# Power_Supply.net
KiCad netlist of a schematic drawn in Altium Designer
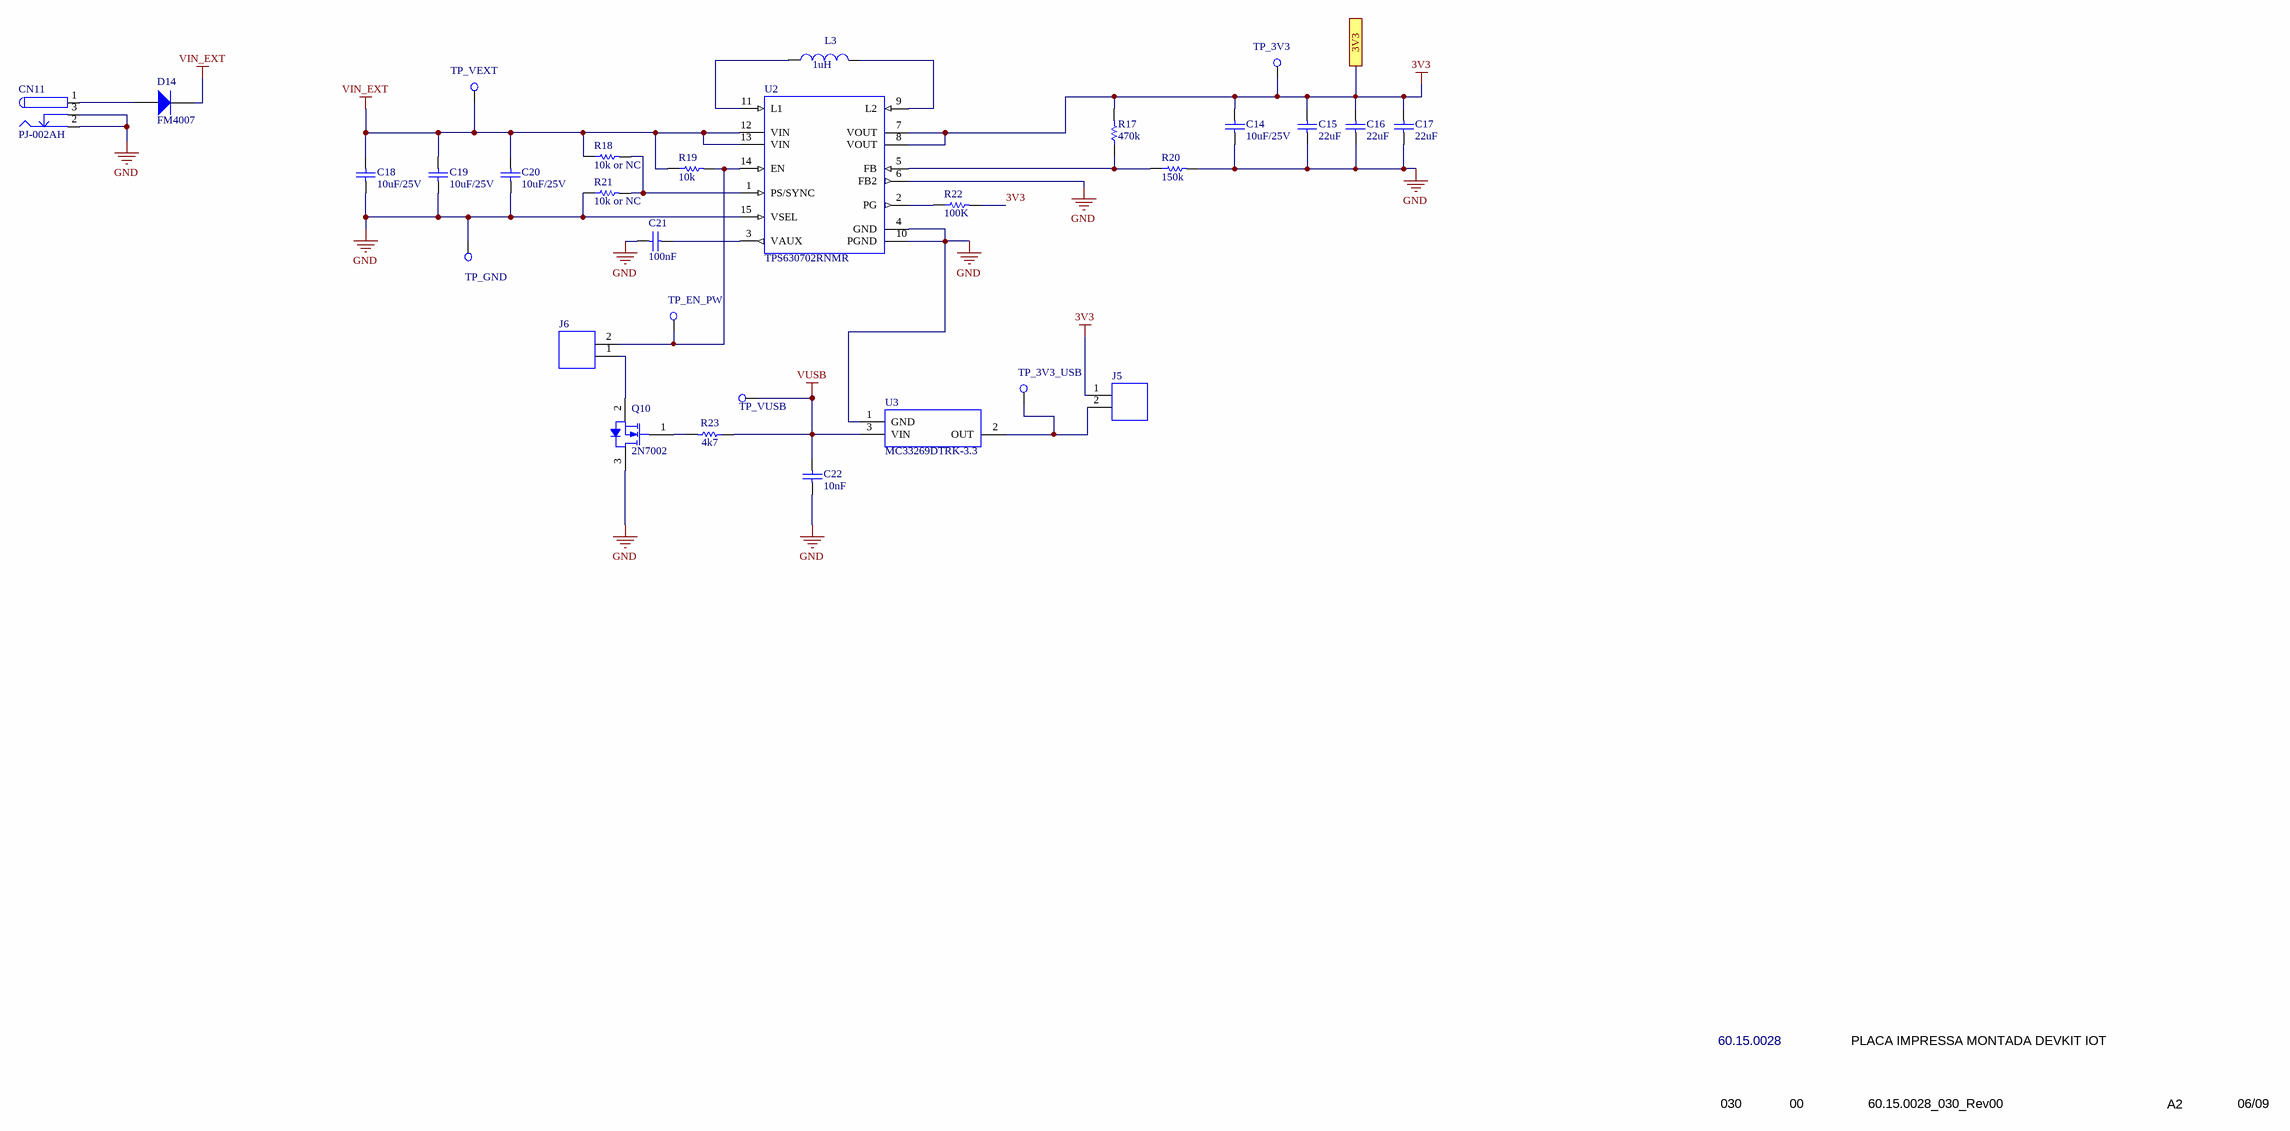
[diagram p0: Power Supply.SchDoc]

(export (version "E")
  (design (tool "Eeschema 10.0.6"))
  (components
    (comp (ref "C14")
      (value "10uF/25V")
      (footprint "16.23.0733")
      (description "CAPACITOR CERAMICO MULTICAMADAS 10uF 25V 20% SMD 0603 X5R")
      (fields (field (name "PART NUMBER") "GRM188R61E106MA73") (field (name "Comment") "16.23.0733"))
      (libsource (lib "OMNI-CAPACITORES") (part "16.23.0733"))
    )
    (comp (ref "C15")
      (value "16.23.0428")
      (footprint "16.23.0428")
      (description "CC MUL 22uF 16V X5R 20% SMD 0805")
      (fields (field (name "ALTIUM_UNNAMED_1") "22uF"))
      (libsource (lib "OMNI-CAPACITORES") (part "16.23.0428"))
    )
    (comp (ref "C16")
      (value "16.23.0428")
      (footprint "16.23.0428")
      (description "CC MUL 22uF 16V X5R 20% SMD 0805")
      (fields (field (name "ALTIUM_UNNAMED_1") "22uF"))
      (libsource (lib "OMNI-CAPACITORES") (part "16.23.0428"))
    )
    (comp (ref "C17")
      (value "16.23.0428")
      (footprint "16.23.0428")
      (description "CC MUL 22uF 16V X5R 20% SMD 0805")
      (fields (field (name "ALTIUM_UNNAMED_1") "22uF"))
      (libsource (lib "OMNI-CAPACITORES") (part "16.23.0428"))
    )
    (comp (ref "C18")
      (value "10uF/25V")
      (footprint "16.23.0735")
      (description "CAPACITOR CERAMICO MULTICAMADAS 10uF 25V 10% SMD 0805 X5R")
      (fields (field (name "PART NUMBER") "GRM21BR61E106KA73") (field (name "Comment") "16.23.0735"))
      (libsource (lib "OMNI-CAPACITORES") (part "16.23.0735"))
    )
    (comp (ref "C19")
      (value "10uF/25V")
      (footprint "16.23.0735")
      (description "CAPACITOR CERAMICO MULTICAMADAS 10uF 25V 10% SMD 0805 X5R")
      (fields (field (name "PART NUMBER") "GRM21BR61E106KA73") (field (name "Comment") "16.23.0735"))
      (libsource (lib "OMNI-CAPACITORES") (part "16.23.0735"))
    )
    (comp (ref "C20")
      (value "10uF/25V")
      (footprint "16.23.0733")
      (description "CAPACITOR CERAMICO MULTICAMADAS 10uF 25V 20% SMD 0603 X5R")
      (fields (field (name "PART NUMBER") "GRM188R61E106MA73") (field (name "Comment") "16.23.0733"))
      (libsource (lib "OMNI-CAPACITORES") (part "16.23.0733"))
    )
    (comp (ref "C21")
      (value "100nF")
      (footprint "16.23.0807")
      (description "CAPACITOR CERAMICO MULTICAMADAS 100nF 50V X7R 10% SMD 0402")
      (fields (field (name "Comment") "16.23.0807"))
      (libsource (lib "OMNI-CAPACITORES") (part "16.23.0807"))
    )
    (comp (ref "C22")
      (value "16.23.0427")
      (footprint "16.23.0427")
      (description "CC MUL 10nF 16V C0G 10%  SMD 0402")
      (fields (field (name "ALTIUM_UNNAMED_1") "10nF"))
      (libsource (lib "OMNI-CAPACITORES") (part "16.23.0427"))
    )
    (comp (ref "CN11")
      (value "28.39.0015")
      (footprint "28.39.0015")
      (description "CONECTOR ALIMENTACAO JACK  MODEL PJ-002AH - SMT -TR")
      (fields (field (name "CUI INC") "PJ-002AH"))
      (libsource (lib "OMNI-CONECTORES") (part "28.39.0015"))
    )
    (comp (ref "D14")
      (value "FM4007")
      (footprint "32.21.0028")
      (description "DIODO RETIFICADOR 1A 1000V 1N4007 SMD DO-214AC")
      (fields (field (name "Comment") "32.21.0028"))
      (libsource (lib "OMNI-DIODOS_LED´s_DISPLAYS") (part "32.21.0028"))
    )
    (comp (ref "J5")
      (value "70.11.0010")
      (footprint "70.11.0010")
      (description "BARRA DE TERMINAIS 1x2")
      (libsource (lib "") (part "70.11.0010_1"))
    )
    (comp (ref "J6")
      (value "70.11.0010")
      (footprint "70.11.0010")
      (description "BARRA DE TERMINAIS 1x2")
      (libsource (lib "OMNI-CONECTORES") (part "70.11.0010"))
    )
    (comp (ref "L3")
      (value "1uH")
      (footprint "40.12.0346")
      (description "INDUTOR FIXO 1uH 20% 5A 36mOHM SMD 1008")
      (fields (field (name "Comment") "40.12.0346"))
      (libsource (lib "OMNI-INDUTORES") (part "40.12.0346"))
    )
    (comp (ref "Q10")
      (value "72.19.0021")
      (footprint "72.19.0021")
      (description "TRANSISTOR MOSFET N 60V 115MA 0.2W SMD")
      (fields (field (name "ALTIUM_UNNAMED_1") "2N7002"))
      (libsource (lib "OMNI-TRANSISTORES") (part "72.19.0021"))
    )
    (comp (ref "R17")
      (value "470k")
      (footprint "66.21.1644")
      (description "RESISTOR THICK FILM 470k OHMS 25V 0.05W 1% SMD 0201")
      (fields (field (name "Comment") "66.21.1644"))
      (libsource (lib "OMNI-RESISTORES") (part "66.21.1644"))
    )
    (comp (ref "R18")
      (value "10k or NC")
      (footprint "66.21.1646")
      (description "RESISTOR THICK FILM 10k OHMS 25V 0.05W 1% SMD 0201")
      (fields (field (name "Comment") "66.21.1646"))
      (libsource (lib "OMNI-RESISTORES") (part "66.21.1646"))
    )
    (comp (ref "R19")
      (value "10k")
      (footprint "66.21.1646")
      (description "RESISTOR THICK FILM 10k OHMS 25V 0.05W 1% SMD 0201")
      (fields (field (name "Comment") "66.21.1646"))
      (libsource (lib "OMNI-RESISTORES") (part "66.21.1646"))
    )
    (comp (ref "R20")
      (value "150k")
      (footprint "66.21.1645")
      (description "RESISTOR THICK FILM 150k OHMS 25V 0.05W 1% SMD 0201")
      (fields (field (name "Comment") "66.21.1645"))
      (libsource (lib "OMNI-RESISTORES") (part "66.21.1645"))
    )
    (comp (ref "R21")
      (value "10k or NC")
      (footprint "66.21.1646")
      (description "RESISTOR THICK FILM 10k OHMS 25V 0.05W 1% SMD 0201")
      (fields (field (name "Comment") "66.21.1646"))
      (libsource (lib "OMNI-RESISTORES") (part "66.21.1646"))
    )
    (comp (ref "R22")
      (value "100K")
      (footprint "66.24.1346")
      (description "RESISTOR THICK FILM 50mW 100K OHMS 1% SMD 0201")
      (fields (field (name "Comment") "66.24.1346"))
      (libsource (lib "OMNI-RESISTORES") (part "66.24.1346"))
    )
    (comp (ref "R23")
      (value "4k7")
      (footprint "66.24.1353")
      (description "RESISTOR THICK FILM 4k7 kOHMS 50V 0,1W 1% SMD 0402")
      (fields (field (name "PART NUMBER") "ERJ-2RKF4701X") (field (name "Comment") "66.24.1353"))
      (libsource (lib "OMNI-RESISTORES") (part "66.24.1353"))
    )
    (comp (ref "TP_3V3")
      (value "TESTPOINT")
      (footprint "TESTPOINT-60MILS")
      (description "PONTO DE TESTE PARA CAMA DE PREGO")
      (libsource (lib "OMNI-SEM-COD") (part "TESTPOINT-60MILS"))
    )
    (comp (ref "TP_3V3_USB")
      (value "TESTPOINT")
      (footprint "TESTPOINT-60MILS")
      (description "PONTO DE TESTE PARA CAMA DE PREGO")
      (libsource (lib "OMNI-SEM-COD") (part "TESTPOINT-60MILS"))
    )
    (comp (ref "TP_EN_PW")
      (value "TESTPOINT")
      (footprint "TESTPOINT-60MILS")
      (description "PONTO DE TESTE PARA CAMA DE PREGO")
      (libsource (lib "OMNI-SEM-COD") (part "TESTPOINT-60MILS"))
    )
    (comp (ref "TP_GND")
      (value "TESTPOINT")
      (footprint "TESTPOINT-60MILS")
      (description "PONTO DE TESTE PARA CAMA DE PREGO")
      (libsource (lib "OMNI-SEM-COD") (part "TESTPOINT-60MILS"))
    )
    (comp (ref "TP_VEXT")
      (value "TESTPOINT")
      (footprint "TESTPOINT-60MILS")
      (description "PONTO DE TESTE PARA CAMA DE PREGO")
      (libsource (lib "OMNI-SEM-COD") (part "TESTPOINT-60MILS"))
    )
    (comp (ref "TP_VUSB")
      (value "TESTPOINT")
      (footprint "TESTPOINT-60MILS")
      (description "PONTO DE TESTE PARA CAMA DE PREGO")
      (libsource (lib "OMNI-SEM-COD") (part "TESTPOINT-60MILS"))
    )
    (comp (ref "U2")
      (value "TPS630702RNMR")
      (footprint "26.24.0200")
      (description "CI REGULADOR TENSAO CHAV AJUST 2A16V 2A DESC SAIDA VQFN-HR")
      (fields (field (name "Comment") "26.24.0200"))
      (libsource (lib "OMNI-CI´S ANALÓGICOS") (part "26.24.0200"))
    )
    (comp (ref "U3")
      (value "MC33269DTRK-3.3")
      (footprint "26.24.0067")
      (description "CIL REGULADOR DE TENSAO 3.3V SMD")
      (fields (field (name "Comment") "26.24.0067"))
      (libsource (lib "OMNI-CI´S ANALÓGICOS") (part "26.24.0067"))
    )
  )
  (nets
    (net (code "1") (name "3V3") (class "Default")
      (node (ref "C14") (pin "2") (pinfunction "2_2") (pintype "passive"))
      (node (ref "C15") (pin "2") (pinfunction "2_2") (pintype "passive"))
      (node (ref "C16") (pin "2") (pinfunction "2_2") (pintype "passive"))
      (node (ref "C17") (pin "2") (pinfunction "2_2") (pintype "passive"))
      (node (ref "J5") (pin "1") (pinfunction "1_1") (pintype "passive"))
      (node (ref "R17") (pin "2") (pinfunction "2_2") (pintype "passive"))
      (node (ref "R22") (pin "2") (pinfunction "2_2") (pintype "passive"))
      (node (ref "TP_3V3") (pin "1") (pinfunction "TP_1") (pintype "passive"))
      (node (ref "U2") (pin "7") (pinfunction "VOUT_7") (pintype "power_in"))
      (node (ref "U2") (pin "8") (pinfunction "VOUT_8") (pintype "power_in"))
    )
    (net (code "2") (name "GND") (class "Default")
      (node (ref "C14") (pin "1") (pinfunction "1_1") (pintype "passive"))
      (node (ref "C15") (pin "1") (pinfunction "1_1") (pintype "passive"))
      (node (ref "C16") (pin "1") (pinfunction "1_1") (pintype "passive"))
      (node (ref "C17") (pin "1") (pinfunction "1_1") (pintype "passive"))
      (node (ref "C18") (pin "1") (pinfunction "1_1") (pintype "passive"))
      (node (ref "C19") (pin "1") (pinfunction "1_1") (pintype "passive"))
      (node (ref "C20") (pin "1") (pinfunction "1_1") (pintype "passive"))
      (node (ref "C21") (pin "1") (pinfunction "1_1") (pintype "passive"))
      (node (ref "C22") (pin "2") (pinfunction "2_2") (pintype "passive"))
      (node (ref "CN11") (pin "2") (pinfunction "2_2") (pintype "power_in"))
      (node (ref "CN11") (pin "3") (pinfunction "3_3") (pintype "power_in"))
      (node (ref "Q10") (pin "3") (pinfunction "D_3") (pintype "passive"))
      (node (ref "R20") (pin "2") (pinfunction "2_2") (pintype "passive"))
      (node (ref "R21") (pin "1") (pinfunction "1_1") (pintype "passive"))
      (node (ref "TP_GND") (pin "1") (pinfunction "TP_1") (pintype "passive"))
      (node (ref "U2") (pin "10") (pinfunction "PGND_10") (pintype "power_in"))
      (node (ref "U2") (pin "15") (pinfunction "VSEL_15") (pintype "input"))
      (node (ref "U2") (pin "4") (pinfunction "GND_4") (pintype "passive"))
      (node (ref "U2") (pin "6") (pinfunction "FB2_6") (pintype "output"))
      (node (ref "U3") (pin "1") (pinfunction "GND_1") (pintype "power_in"))
    )
    (net (code "3") (name "Net-(CN11-Pad1)") (class "Default")
      (node (ref "CN11") (pin "1") (pinfunction "1_1") (pintype "power_in"))
      (node (ref "D14") (pin "A") (pinfunction "A_A") (pintype "passive"))
    )
    (net (code "4") (name "Net-(Q10-G)") (class "Default")
      (node (ref "Q10") (pin "1") (pinfunction "G_1") (pintype "passive"))
      (node (ref "R23") (pin "2") (pinfunction "2_2") (pintype "passive"))
    )
    (net (code "5") (name "Net-(Q10-S)") (class "Default")
      (node (ref "J6") (pin "1") (pinfunction "1_1") (pintype "passive"))
      (node (ref "Q10") (pin "2") (pinfunction "S_2") (pintype "passive"))
    )
    (net (code "6") (name "Net-(TP_3V3_USB-TP)") (class "Default")
      (node (ref "J5") (pin "2") (pinfunction "2_2") (pintype "passive"))
      (node (ref "TP_3V3_USB") (pin "1") (pinfunction "TP_1") (pintype "passive"))
      (node (ref "U3") (pin "2") (pinfunction "OUT_2") (pintype "power_in"))
    )
    (net (code "7") (name "Net-(TP_EN_PW-TP)") (class "Default")
      (node (ref "J6") (pin "2") (pinfunction "2_2") (pintype "passive"))
      (node (ref "R19") (pin "2") (pinfunction "2_2") (pintype "passive"))
      (node (ref "TP_EN_PW") (pin "1") (pinfunction "TP_1") (pintype "passive"))
      (node (ref "U2") (pin "14") (pinfunction "EN_14") (pintype "input"))
    )
    (net (code "8") (name "Net-(U2-FB)") (class "Default")
      (node (ref "R17") (pin "1") (pinfunction "1_1") (pintype "passive"))
      (node (ref "R20") (pin "1") (pinfunction "1_1") (pintype "passive"))
      (node (ref "U2") (pin "5") (pinfunction "FB_5") (pintype "input"))
    )
    (net (code "9") (name "Net-(U2-L1)") (class "Default")
      (node (ref "L3") (pin "1") (pinfunction "1_1") (pintype "passive"))
      (node (ref "U2") (pin "11") (pinfunction "L1_11") (pintype "input"))
    )
    (net (code "10") (name "Net-(U2-L2)") (class "Default")
      (node (ref "L3") (pin "2") (pinfunction "2_2") (pintype "passive"))
      (node (ref "U2") (pin "9") (pinfunction "L2_9") (pintype "input"))
    )
    (net (code "11") (name "Net-(U2-PG)") (class "Default")
      (node (ref "R22") (pin "1") (pinfunction "1_1") (pintype "passive"))
      (node (ref "U2") (pin "2") (pinfunction "PG_2") (pintype "output"))
    )
    (net (code "12") (name "Net-(U2-PS{slash}SYNC)") (class "Default")
      (node (ref "R18") (pin "2") (pinfunction "2_2") (pintype "passive"))
      (node (ref "R21") (pin "2") (pinfunction "2_2") (pintype "passive"))
      (node (ref "U2") (pin "1") (pinfunction "PS/SYNC_1") (pintype "input"))
    )
    (net (code "13") (name "Net-(U2-VAUX)") (class "Default")
      (node (ref "C21") (pin "2") (pinfunction "2_2") (pintype "passive"))
      (node (ref "U2") (pin "3") (pinfunction "VAUX_3") (pintype "output"))
    )
    (net (code "14") (name "VIN_EXT") (class "Default")
      (node (ref "C18") (pin "2") (pinfunction "2_2") (pintype "passive"))
      (node (ref "C19") (pin "2") (pinfunction "2_2") (pintype "passive"))
      (node (ref "C20") (pin "2") (pinfunction "2_2") (pintype "passive"))
      (node (ref "D14") (pin "K") (pinfunction "K_K") (pintype "passive"))
      (node (ref "R18") (pin "1") (pinfunction "1_1") (pintype "passive"))
      (node (ref "R19") (pin "1") (pinfunction "1_1") (pintype "passive"))
      (node (ref "TP_VEXT") (pin "1") (pinfunction "TP_1") (pintype "passive"))
      (node (ref "U2") (pin "12") (pinfunction "VIN_12") (pintype "power_in"))
      (node (ref "U2") (pin "13") (pinfunction "VIN_13") (pintype "power_in"))
    )
    (net (code "15") (name "VUSB") (class "Default")
      (node (ref "C22") (pin "1") (pinfunction "1_1") (pintype "passive"))
      (node (ref "R23") (pin "1") (pinfunction "1_1") (pintype "passive"))
      (node (ref "TP_VUSB") (pin "1") (pinfunction "TP_1") (pintype "passive"))
      (node (ref "U3") (pin "3") (pinfunction "VIN_3") (pintype "power_in"))
    )
  )
)
